# Regulator.net
KiCad netlist of a schematic drawn in Altium Designer
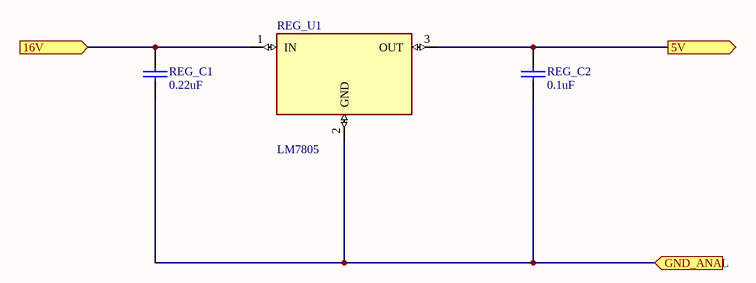
[diagram p0: Regulator.SchDoc]

(export (version "E")
  (design (tool "Eeschema 10.0.6"))
  (components
    (comp (ref "REG_C1") (value "0.22uF") (footprint "CAP200") (libsource (lib "LIBEBAL") (part "CAP")))
    (comp (ref "REG_C2") (value "0.1uF") (footprint "CAP200") (libsource (lib "LIBEBAL") (part "CAP")))
    (comp (ref "REG_U1")
      (value "LM7805")
      (footprint "TO220")
      (description "Linear Voltage Regulator IC 1 Output 1.5A SOT-223-4")
      (fields (field (name "MF") "Texas Instruments"))
      (libsource (lib "LM7805") (part "LM7805"))
    )
  )
  (nets
    (net (code "1") (name "/5V") (class "Default")
      (node (ref "REG_C2") (pin "1") (pinfunction "1_1") (pintype "passive"))
      (node (ref "REG_U1") (pin "3") (pinfunction "OUT_3") (pintype "bidirectional"))
    )
    (net (code "2") (name "/16V") (class "Default")
      (node (ref "REG_C1") (pin "1") (pinfunction "1_1") (pintype "passive"))
      (node (ref "REG_U1") (pin "1") (pinfunction "IN_1") (pintype "bidirectional"))
    )
    (net (code "3") (name "/GND_ANAL") (class "Default")
      (node (ref "REG_C1") (pin "2") (pinfunction "2_2") (pintype "passive"))
      (node (ref "REG_C2") (pin "2") (pinfunction "2_2") (pintype "passive"))
      (node (ref "REG_U1") (pin "2") (pinfunction "GND_2") (pintype "bidirectional"))
    )
  )
)
